# 06_ULTRA_WIDEBAND.net
KiCad netlist of a schematic drawn in Altium Designer
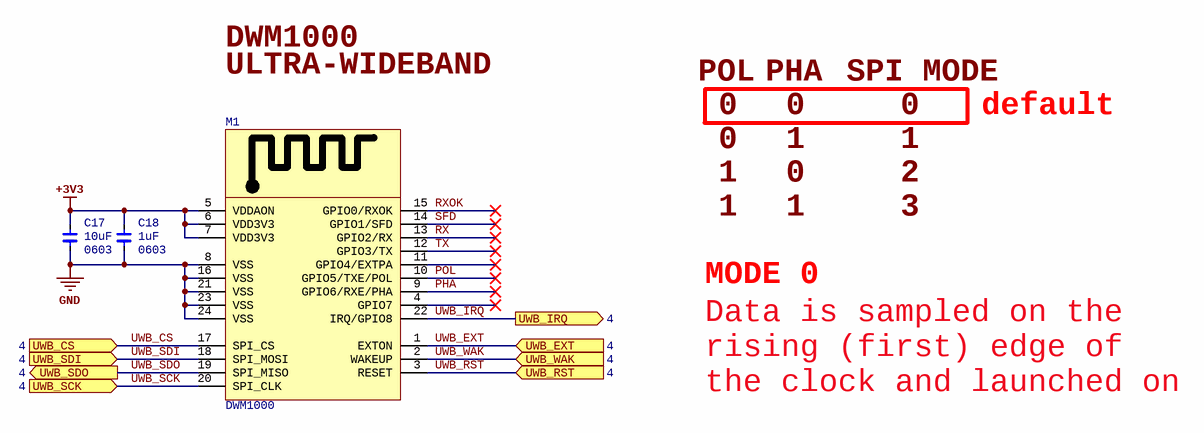
[diagram p0: [06] ULTRA WIDEBAND.SchDoc]

(export (version "E")
  (design (tool "Eeschema 10.0.6"))
  (components
    (comp (ref "C17")
      (value "10uF")
      (footprint "PCB_PassiveCap:CAP_0603")
      (description "Capacitor")
      (fields (field (name "TYPE") "0603"))
      (libsource (lib "SCH_Passive") (part "Cap_0603"))
    )
    (comp (ref "C18")
      (value "1uF")
      (footprint "PCB_PassiveCap:CAP_0603")
      (description "Capacitor")
      (fields (field (name "TYPE") "0603"))
      (libsource (lib "SCH_Passive") (part "Cap_0603"))
    )
    (comp (ref "M1")
      (value "DWM1000")
      (footprint "PCB_Module:DWM1000")
      (description "Module")
      (fields (field (name "MANUFACTURER") "Decawave Limited"))
      (libsource (lib "SCH_Module") (part "DWM1000"))
    )
  )
  (nets
    (net (code "1") (name "+3V3") (class "Default")
      (node (ref "C17") (pin "2") (pinfunction "2_2") (pintype "passive"))
      (node (ref "C18") (pin "2") (pinfunction "2_2") (pintype "passive"))
      (node (ref "M1") (pin "5") (pinfunction "VDDAON_5") (pintype "passive"))
      (node (ref "M1") (pin "6") (pinfunction "VDD3V3_6") (pintype "passive"))
      (node (ref "M1") (pin "7") (pinfunction "VDD3V3_7") (pintype "passive"))
    )
    (net (code "2") (name "/PHA") (class "Default")
      (node (ref "M1") (pin "9") (pinfunction "GPIO6/RXE/PHA_9") (pintype "passive+no_connect"))
    )
    (net (code "3") (name "/POL") (class "Default")
      (node (ref "M1") (pin "10") (pinfunction "GPIO5/TXE/POL_10") (pintype "passive+no_connect"))
    )
    (net (code "4") (name "/RX") (class "Default")
      (node (ref "M1") (pin "13") (pinfunction "GPIO2/RX_13") (pintype "passive+no_connect"))
    )
    (net (code "5") (name "/RXOK") (class "Default")
      (node (ref "M1") (pin "15") (pinfunction "GPIO0/RXOK_15") (pintype "passive+no_connect"))
    )
    (net (code "6") (name "/SFD") (class "Default")
      (node (ref "M1") (pin "14") (pinfunction "GPIO1/SFD_14") (pintype "passive+no_connect"))
    )
    (net (code "7") (name "/TX") (class "Default")
      (node (ref "M1") (pin "12") (pinfunction "GPIO3/TX_12") (pintype "passive+no_connect"))
    )
    (net (code "8") (name "/UWB_CS") (class "Default")
      (node (ref "M1") (pin "17") (pinfunction "SPI_CS_17") (pintype "passive"))
    )
    (net (code "9") (name "/UWB_EXT") (class "Default")
      (node (ref "M1") (pin "1") (pinfunction "EXTON_1") (pintype "passive"))
    )
    (net (code "10") (name "/UWB_IRQ") (class "Default")
      (node (ref "M1") (pin "22") (pinfunction "IRQ/GPIO8_22") (pintype "passive"))
    )
    (net (code "11") (name "/UWB_RST") (class "Default")
      (node (ref "M1") (pin "3") (pinfunction "RESET_3") (pintype "passive"))
    )
    (net (code "12") (name "/UWB_SCK") (class "Default")
      (node (ref "M1") (pin "20") (pinfunction "SPI_CLK_20") (pintype "passive"))
    )
    (net (code "13") (name "/UWB_SDI") (class "Default")
      (node (ref "M1") (pin "18") (pinfunction "SPI_MOSI_18") (pintype "passive"))
    )
    (net (code "14") (name "/UWB_SDO") (class "Default")
      (node (ref "M1") (pin "19") (pinfunction "SPI_MISO_19") (pintype "passive"))
    )
    (net (code "15") (name "/UWB_WAK") (class "Default")
      (node (ref "M1") (pin "2") (pinfunction "WAKEUP_2") (pintype "passive"))
    )
    (net (code "16") (name "GND") (class "Default")
      (node (ref "C17") (pin "1") (pinfunction "1_1") (pintype "passive"))
      (node (ref "C18") (pin "1") (pinfunction "1_1") (pintype "passive"))
      (node (ref "M1") (pin "16") (pinfunction "VSS_16") (pintype "passive"))
      (node (ref "M1") (pin "21") (pinfunction "VSS_21") (pintype "passive"))
      (node (ref "M1") (pin "23") (pinfunction "VSS_23") (pintype "passive"))
      (node (ref "M1") (pin "24") (pinfunction "VSS_24") (pintype "passive"))
      (node (ref "M1") (pin "8") (pinfunction "VSS_8") (pintype "passive"))
    )
    (net (code "17") (name "unconnected-(M1-GPIO4{slash}EXTPA-Pad11)") (class "Default")
      (node (ref "M1") (pin "11") (pinfunction "GPIO4/EXTPA_11") (pintype "passive+no_connect"))
    )
    (net (code "18") (name "unconnected-(M1-GPIO7-Pad4)") (class "Default")
      (node (ref "M1") (pin "4") (pinfunction "GPIO7_4") (pintype "passive+no_connect"))
    )
  )
)
